# THW_Schematic_v1_0_0.net
KiCad netlist of a schematic drawn in EAGLE
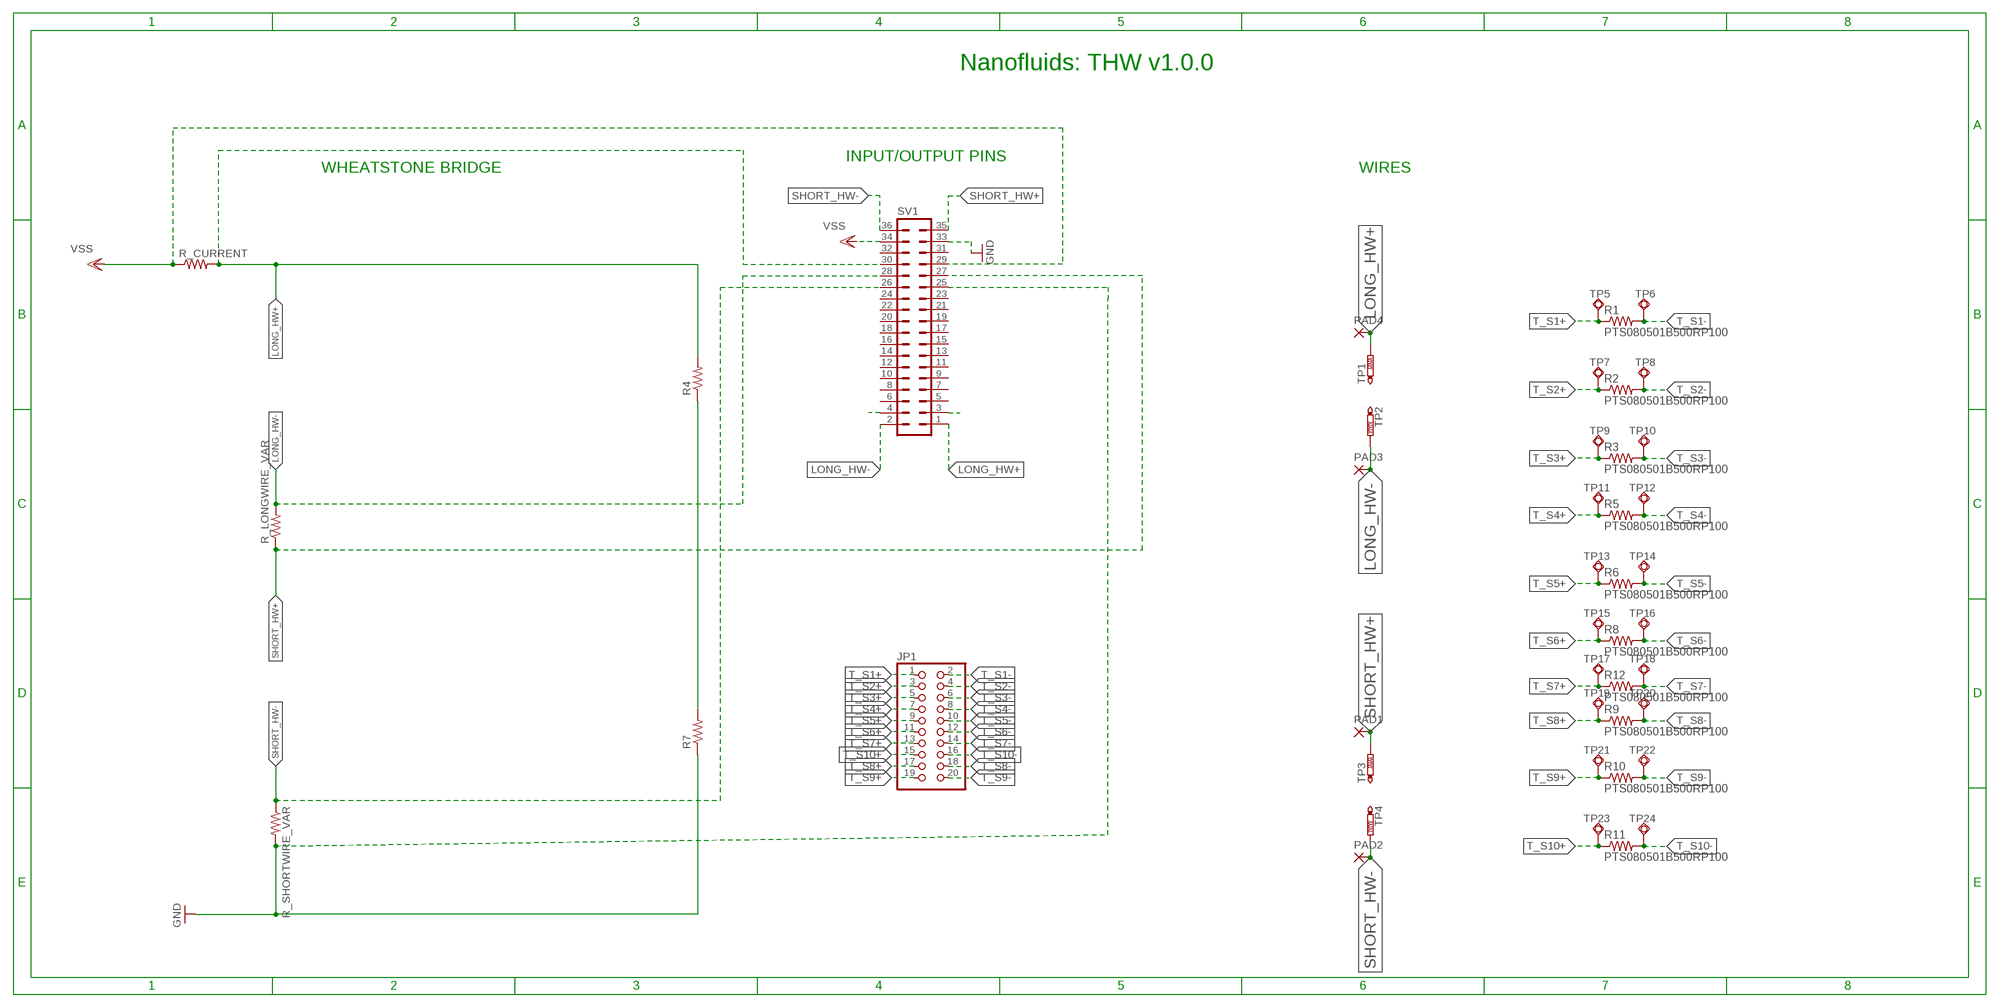
[diagram p0: schematic, sheet 1]

(export (version "E")
  (design (tool "Eeschema 10.0.6"))
  (components
    (comp (ref "JP1")
      (value "PINHD-2X10")
      (footprint "eagle-import:2X10")
      (libsource (lib "eagle-import") (part "PINHD-2X10"))
    )
    (comp (ref "PAD1")
      (value "SMD5")
      (footprint "eagle-import:SMD2,54-5,08")
      (libsource (lib "eagle-import") (part "SMD5"))
    )
    (comp (ref "PAD2")
      (value "SMD5")
      (footprint "eagle-import:SMD2,54-5,08")
      (libsource (lib "eagle-import") (part "SMD5"))
    )
    (comp (ref "PAD3")
      (value "SMD5")
      (footprint "eagle-import:SMD2,54-5,08")
      (libsource (lib "eagle-import") (part "SMD5"))
    )
    (comp (ref "PAD4")
      (value "SMD5")
      (footprint "eagle-import:SMD2,54-5,08")
      (libsource (lib "eagle-import") (part "SMD5"))
    )
    (comp (ref "R1")
      (value "PTS080501B500RP100")
      (footprint "eagle-import:RESC2012X60")
      (fields (field (name "MF") "Vishay"))
      (libsource (lib "eagle-import") (part "PTS080501B500RP100"))
    )
    (comp (ref "R2")
      (value "PTS080501B500RP100")
      (footprint "eagle-import:RESC2012X60")
      (fields (field (name "MF") "Vishay"))
      (libsource (lib "eagle-import") (part "PTS080501B500RP100"))
    )
    (comp (ref "R3")
      (value "PTS080501B500RP100")
      (footprint "eagle-import:RESC2012X60")
      (fields (field (name "MF") "Vishay"))
      (libsource (lib "eagle-import") (part "PTS080501B500RP100"))
    )
    (comp (ref "R4")
      (value "R-US_M0805")
      (footprint "eagle-import:M0805")
      (libsource (lib "eagle-import") (part "R-US_M0805"))
    )
    (comp (ref "R5")
      (value "PTS080501B500RP100")
      (footprint "eagle-import:RESC2012X60")
      (fields (field (name "MF") "Vishay"))
      (libsource (lib "eagle-import") (part "PTS080501B500RP100"))
    )
    (comp (ref "R6")
      (value "PTS080501B500RP100")
      (footprint "eagle-import:RESC2012X60")
      (fields (field (name "MF") "Vishay"))
      (libsource (lib "eagle-import") (part "PTS080501B500RP100"))
    )
    (comp (ref "R7")
      (value "R-US_M0805")
      (footprint "eagle-import:M0805")
      (libsource (lib "eagle-import") (part "R-US_M0805"))
    )
    (comp (ref "R8")
      (value "PTS080501B500RP100")
      (footprint "eagle-import:RESC2012X60")
      (fields (field (name "MF") "Vishay"))
      (libsource (lib "eagle-import") (part "PTS080501B500RP100"))
    )
    (comp (ref "R9")
      (value "PTS080501B500RP100")
      (footprint "eagle-import:RESC2012X60")
      (fields (field (name "MF") "Vishay"))
      (libsource (lib "eagle-import") (part "PTS080501B500RP100"))
    )
    (comp (ref "R10")
      (value "PTS080501B500RP100")
      (footprint "eagle-import:RESC2012X60")
      (fields (field (name "MF") "Vishay"))
      (libsource (lib "eagle-import") (part "PTS080501B500RP100"))
    )
    (comp (ref "R11")
      (value "PTS080501B500RP100")
      (footprint "eagle-import:RESC2012X60")
      (fields (field (name "MF") "Vishay"))
      (libsource (lib "eagle-import") (part "PTS080501B500RP100"))
    )
    (comp (ref "R12")
      (value "PTS080501B500RP100")
      (footprint "eagle-import:RESC2012X60")
      (fields (field (name "MF") "Vishay"))
      (libsource (lib "eagle-import") (part "PTS080501B500RP100"))
    )
    (comp (ref "R_CURRENT")
      (value "R-US_M0805")
      (footprint "eagle-import:M0805")
      (libsource (lib "eagle-import") (part "R-US_M0805"))
    )
    (comp (ref "R_LONGWIRE_VAR")
      (value "R-US_M0805")
      (footprint "eagle-import:M0805")
      (libsource (lib "eagle-import") (part "R-US_M0805"))
    )
    (comp (ref "R_SHORTWIRE_VAR")
      (value "R-US_M0805")
      (footprint "eagle-import:M0805")
      (libsource (lib "eagle-import") (part "R-US_M0805"))
    )
    (comp (ref "SV1")
      (value "MA18-2")
      (footprint "eagle-import:MA18-2")
      (libsource (lib "eagle-import") (part "MA18-2"))
    )
    (comp (ref "TP1")
      (value "PTR1TP20R")
      (footprint "eagle-import:TP20R")
      (libsource (lib "eagle-import") (part "PTR1TP20R"))
    )
    (comp (ref "TP2")
      (value "PTR1TP20R")
      (footprint "eagle-import:TP20R")
      (libsource (lib "eagle-import") (part "PTR1TP20R"))
    )
    (comp (ref "TP3")
      (value "PTR1TP20R")
      (footprint "eagle-import:TP20R")
      (libsource (lib "eagle-import") (part "PTR1TP20R"))
    )
    (comp (ref "TP4")
      (value "PTR1TP20R")
      (footprint "eagle-import:TP20R")
      (libsource (lib "eagle-import") (part "PTR1TP20R"))
    )
    (comp (ref "TP5")
      (value "TPSQTP09SQ")
      (footprint "eagle-import:TP09SQ")
      (libsource (lib "eagle-import") (part "TPSQTP09SQ"))
    )
    (comp (ref "TP6")
      (value "TPSQTP09SQ")
      (footprint "eagle-import:TP09SQ")
      (libsource (lib "eagle-import") (part "TPSQTP09SQ"))
    )
    (comp (ref "TP7")
      (value "TPSQTP09SQ")
      (footprint "eagle-import:TP09SQ")
      (libsource (lib "eagle-import") (part "TPSQTP09SQ"))
    )
    (comp (ref "TP8")
      (value "TPSQTP09SQ")
      (footprint "eagle-import:TP09SQ")
      (libsource (lib "eagle-import") (part "TPSQTP09SQ"))
    )
    (comp (ref "TP9")
      (value "TPSQTP09SQ")
      (footprint "eagle-import:TP09SQ")
      (libsource (lib "eagle-import") (part "TPSQTP09SQ"))
    )
    (comp (ref "TP10")
      (value "TPSQTP09SQ")
      (footprint "eagle-import:TP09SQ")
      (libsource (lib "eagle-import") (part "TPSQTP09SQ"))
    )
    (comp (ref "TP11")
      (value "TPSQTP09SQ")
      (footprint "eagle-import:TP09SQ")
      (libsource (lib "eagle-import") (part "TPSQTP09SQ"))
    )
    (comp (ref "TP12")
      (value "TPSQTP09SQ")
      (footprint "eagle-import:TP09SQ")
      (libsource (lib "eagle-import") (part "TPSQTP09SQ"))
    )
    (comp (ref "TP13")
      (value "TPSQTP09SQ")
      (footprint "eagle-import:TP09SQ")
      (libsource (lib "eagle-import") (part "TPSQTP09SQ"))
    )
    (comp (ref "TP14")
      (value "TPSQTP09SQ")
      (footprint "eagle-import:TP09SQ")
      (libsource (lib "eagle-import") (part "TPSQTP09SQ"))
    )
    (comp (ref "TP15")
      (value "TPSQTP09SQ")
      (footprint "eagle-import:TP09SQ")
      (libsource (lib "eagle-import") (part "TPSQTP09SQ"))
    )
    (comp (ref "TP16")
      (value "TPSQTP09SQ")
      (footprint "eagle-import:TP09SQ")
      (libsource (lib "eagle-import") (part "TPSQTP09SQ"))
    )
    (comp (ref "TP17")
      (value "TPSQTP09SQ")
      (footprint "eagle-import:TP09SQ")
      (libsource (lib "eagle-import") (part "TPSQTP09SQ"))
    )
    (comp (ref "TP18")
      (value "TPSQTP09SQ")
      (footprint "eagle-import:TP09SQ")
      (libsource (lib "eagle-import") (part "TPSQTP09SQ"))
    )
    (comp (ref "TP19")
      (value "TPSQTP09SQ")
      (footprint "eagle-import:TP09SQ")
      (libsource (lib "eagle-import") (part "TPSQTP09SQ"))
    )
    (comp (ref "TP20")
      (value "TPSQTP09SQ")
      (footprint "eagle-import:TP09SQ")
      (libsource (lib "eagle-import") (part "TPSQTP09SQ"))
    )
    (comp (ref "TP21")
      (value "TPSQTP09SQ")
      (footprint "eagle-import:TP09SQ")
      (libsource (lib "eagle-import") (part "TPSQTP09SQ"))
    )
    (comp (ref "TP22")
      (value "TPSQTP09SQ")
      (footprint "eagle-import:TP09SQ")
      (libsource (lib "eagle-import") (part "TPSQTP09SQ"))
    )
    (comp (ref "TP23")
      (value "TPSQTP09SQ")
      (footprint "eagle-import:TP09SQ")
      (libsource (lib "eagle-import") (part "TPSQTP09SQ"))
    )
    (comp (ref "TP24")
      (value "TPSQTP09SQ")
      (footprint "eagle-import:TP09SQ")
      (libsource (lib "eagle-import") (part "TPSQTP09SQ"))
    )
  )
  (nets
    (net (code "1") (name "GND") (class "Default")
      (node (ref "R7") (pin "1") (pinfunction "1_1") (pintype "passive"))
      (node (ref "R_SHORTWIRE_VAR") (pin "2") (pinfunction "2_2") (pintype "passive"))
      (node (ref "SV1") (pin "25") (pinfunction "25_25") (pintype "passive"))
      (node (ref "SV1") (pin "33") (pinfunction "33_33") (pintype "passive"))
    )
    (net (code "2") (name "LONG_HW+") (class "Default")
      (node (ref "PAD4") (pin "1") (pinfunction "P_1") (pintype "passive"))
      (node (ref "R4") (pin "2") (pinfunction "2_2") (pintype "passive"))
      (node (ref "R_CURRENT") (pin "2") (pinfunction "2_2") (pintype "passive"))
      (node (ref "SV1") (pin "1") (pinfunction "1_1") (pintype "passive"))
      (node (ref "SV1") (pin "30") (pinfunction "30_30") (pintype "passive"))
      (node (ref "TP1") (pin "TP") (pinfunction "TP_TP") (pintype "input"))
    )
    (net (code "3") (name "LONG_HW-") (class "Default")
      (node (ref "PAD3") (pin "1") (pinfunction "P_1") (pintype "passive"))
      (node (ref "R_LONGWIRE_VAR") (pin "2") (pinfunction "2_2") (pintype "passive"))
      (node (ref "SV1") (pin "2") (pinfunction "2_2") (pintype "passive"))
      (node (ref "SV1") (pin "28") (pinfunction "28_28") (pintype "passive"))
      (node (ref "TP2") (pin "TP") (pinfunction "TP_TP") (pintype "input"))
    )
    (net (code "4") (name "Net-(R4-Pad1)") (class "Default")
      (node (ref "R4") (pin "1") (pinfunction "1_1") (pintype "passive"))
      (node (ref "R7") (pin "2") (pinfunction "2_2") (pintype "passive"))
    )
    (net (code "5") (name "SHORT_HW+") (class "Default")
      (node (ref "PAD1") (pin "1") (pinfunction "P_1") (pintype "passive"))
      (node (ref "R_LONGWIRE_VAR") (pin "1") (pinfunction "1_1") (pintype "passive"))
      (node (ref "SV1") (pin "27") (pinfunction "27_27") (pintype "passive"))
      (node (ref "SV1") (pin "35") (pinfunction "35_35") (pintype "passive"))
      (node (ref "TP3") (pin "TP") (pinfunction "TP_TP") (pintype "input"))
    )
    (net (code "6") (name "SHORT_HW-") (class "Default")
      (node (ref "PAD2") (pin "1") (pinfunction "P_1") (pintype "passive"))
      (node (ref "R_SHORTWIRE_VAR") (pin "1") (pinfunction "1_1") (pintype "passive"))
      (node (ref "SV1") (pin "26") (pinfunction "26_26") (pintype "passive"))
      (node (ref "SV1") (pin "36") (pinfunction "36_36") (pintype "passive"))
      (node (ref "TP4") (pin "TP") (pinfunction "TP_TP") (pintype "input"))
    )
    (net (code "7") (name "T_S1+") (class "Default")
      (node (ref "JP1") (pin "1") (pinfunction "1_1") (pintype "passive"))
      (node (ref "R1") (pin "1") (pinfunction "1_1") (pintype "passive"))
      (node (ref "TP5") (pin "TP") (pinfunction "TP_TP") (pintype "input"))
    )
    (net (code "8") (name "T_S1-") (class "Default")
      (node (ref "JP1") (pin "2") (pinfunction "2_2") (pintype "passive"))
      (node (ref "R1") (pin "2") (pinfunction "2_2") (pintype "passive"))
      (node (ref "TP6") (pin "TP") (pinfunction "TP_TP") (pintype "input"))
    )
    (net (code "9") (name "T_S2+") (class "Default")
      (node (ref "JP1") (pin "3") (pinfunction "3_3") (pintype "passive"))
      (node (ref "R2") (pin "1") (pinfunction "1_1") (pintype "passive"))
      (node (ref "TP7") (pin "TP") (pinfunction "TP_TP") (pintype "input"))
    )
    (net (code "10") (name "T_S2-") (class "Default")
      (node (ref "JP1") (pin "4") (pinfunction "4_4") (pintype "passive"))
      (node (ref "R2") (pin "2") (pinfunction "2_2") (pintype "passive"))
      (node (ref "TP8") (pin "TP") (pinfunction "TP_TP") (pintype "input"))
    )
    (net (code "11") (name "T_S3+") (class "Default")
      (node (ref "JP1") (pin "5") (pinfunction "5_5") (pintype "passive"))
      (node (ref "R3") (pin "1") (pinfunction "1_1") (pintype "passive"))
      (node (ref "TP9") (pin "TP") (pinfunction "TP_TP") (pintype "input"))
    )
    (net (code "12") (name "T_S3-") (class "Default")
      (node (ref "JP1") (pin "6") (pinfunction "6_6") (pintype "passive"))
      (node (ref "R3") (pin "2") (pinfunction "2_2") (pintype "passive"))
      (node (ref "TP10") (pin "TP") (pinfunction "TP_TP") (pintype "input"))
    )
    (net (code "13") (name "T_S4+") (class "Default")
      (node (ref "JP1") (pin "7") (pinfunction "7_7") (pintype "passive"))
      (node (ref "R5") (pin "1") (pinfunction "1_1") (pintype "passive"))
      (node (ref "TP11") (pin "TP") (pinfunction "TP_TP") (pintype "input"))
    )
    (net (code "14") (name "T_S4-") (class "Default")
      (node (ref "JP1") (pin "8") (pinfunction "8_8") (pintype "passive"))
      (node (ref "R5") (pin "2") (pinfunction "2_2") (pintype "passive"))
      (node (ref "TP12") (pin "TP") (pinfunction "TP_TP") (pintype "input"))
    )
    (net (code "15") (name "T_S5+") (class "Default")
      (node (ref "JP1") (pin "9") (pinfunction "9_9") (pintype "passive"))
      (node (ref "R6") (pin "1") (pinfunction "1_1") (pintype "passive"))
      (node (ref "TP13") (pin "TP") (pinfunction "TP_TP") (pintype "input"))
    )
    (net (code "16") (name "T_S5-") (class "Default")
      (node (ref "JP1") (pin "10") (pinfunction "10_10") (pintype "passive"))
      (node (ref "R6") (pin "2") (pinfunction "2_2") (pintype "passive"))
      (node (ref "TP14") (pin "TP") (pinfunction "TP_TP") (pintype "input"))
    )
    (net (code "17") (name "T_S6+") (class "Default")
      (node (ref "JP1") (pin "11") (pinfunction "11_11") (pintype "passive"))
      (node (ref "R8") (pin "1") (pinfunction "1_1") (pintype "passive"))
      (node (ref "TP15") (pin "TP") (pinfunction "TP_TP") (pintype "input"))
    )
    (net (code "18") (name "T_S6-") (class "Default")
      (node (ref "JP1") (pin "12") (pinfunction "12_12") (pintype "passive"))
      (node (ref "R8") (pin "2") (pinfunction "2_2") (pintype "passive"))
      (node (ref "TP16") (pin "TP") (pinfunction "TP_TP") (pintype "input"))
    )
    (net (code "19") (name "T_S7+") (class "Default")
      (node (ref "R12") (pin "1") (pinfunction "1_1") (pintype "passive"))
      (node (ref "TP17") (pin "TP") (pinfunction "TP_TP") (pintype "input"))
    )
    (net (code "20") (name "T_S7-") (class "Default")
      (node (ref "JP1") (pin "14") (pinfunction "14_14") (pintype "passive"))
      (node (ref "R12") (pin "2") (pinfunction "2_2") (pintype "passive"))
      (node (ref "TP18") (pin "TP") (pinfunction "TP_TP") (pintype "input"))
    )
    (net (code "21") (name "T_S8+") (class "Default")
      (node (ref "JP1") (pin "17") (pinfunction "17_17") (pintype "passive"))
      (node (ref "R9") (pin "1") (pinfunction "1_1") (pintype "passive"))
      (node (ref "TP19") (pin "TP") (pinfunction "TP_TP") (pintype "input"))
    )
    (net (code "22") (name "T_S8-") (class "Default")
      (node (ref "JP1") (pin "18") (pinfunction "18_18") (pintype "passive"))
      (node (ref "R9") (pin "2") (pinfunction "2_2") (pintype "passive"))
      (node (ref "TP20") (pin "TP") (pinfunction "TP_TP") (pintype "input"))
    )
    (net (code "23") (name "T_S9+") (class "Default")
      (node (ref "JP1") (pin "19") (pinfunction "19_19") (pintype "passive"))
      (node (ref "R10") (pin "1") (pinfunction "1_1") (pintype "passive"))
      (node (ref "TP21") (pin "TP") (pinfunction "TP_TP") (pintype "input"))
    )
    (net (code "24") (name "T_S9-") (class "Default")
      (node (ref "JP1") (pin "20") (pinfunction "20_20") (pintype "passive"))
      (node (ref "R10") (pin "2") (pinfunction "2_2") (pintype "passive"))
      (node (ref "TP22") (pin "TP") (pinfunction "TP_TP") (pintype "input"))
    )
    (net (code "25") (name "T_S10+") (class "Default")
      (node (ref "JP1") (pin "15") (pinfunction "15_15") (pintype "passive"))
      (node (ref "R11") (pin "1") (pinfunction "1_1") (pintype "passive"))
      (node (ref "TP23") (pin "TP") (pinfunction "TP_TP") (pintype "input"))
    )
    (net (code "26") (name "T_S10-") (class "Default")
      (node (ref "JP1") (pin "16") (pinfunction "16_16") (pintype "passive"))
      (node (ref "R11") (pin "2") (pinfunction "2_2") (pintype "passive"))
      (node (ref "TP24") (pin "TP") (pinfunction "TP_TP") (pintype "input"))
    )
    (net (code "27") (name "VSS") (class "Default")
      (node (ref "R_CURRENT") (pin "1") (pinfunction "1_1") (pintype "passive"))
      (node (ref "SV1") (pin "29") (pinfunction "29_29") (pintype "passive"))
      (node (ref "SV1") (pin "34") (pinfunction "34_34") (pintype "passive"))
    )
    (net (code "28") (name "unconnected-(JP1-Pad13)") (class "Default")
      (node (ref "JP1") (pin "13") (pinfunction "13_13") (pintype "passive"))
    )
    (net (code "29") (name "unconnected-(SV1-Pad3)") (class "Default")
      (node (ref "SV1") (pin "3") (pinfunction "3_3") (pintype "passive"))
    )
    (net (code "30") (name "unconnected-(SV1-Pad4)") (class "Default")
      (node (ref "SV1") (pin "4") (pinfunction "4_4") (pintype "passive"))
    )
    (net (code "31") (name "unconnected-(SV1-Pad5)") (class "Default")
      (node (ref "SV1") (pin "5") (pinfunction "5_5") (pintype "passive"))
    )
    (net (code "32") (name "unconnected-(SV1-Pad6)") (class "Default")
      (node (ref "SV1") (pin "6") (pinfunction "6_6") (pintype "passive"))
    )
    (net (code "33") (name "unconnected-(SV1-Pad7)") (class "Default")
      (node (ref "SV1") (pin "7") (pinfunction "7_7") (pintype "passive"))
    )
    (net (code "34") (name "unconnected-(SV1-Pad8)") (class "Default")
      (node (ref "SV1") (pin "8") (pinfunction "8_8") (pintype "passive"))
    )
    (net (code "35") (name "unconnected-(SV1-Pad9)") (class "Default")
      (node (ref "SV1") (pin "9") (pinfunction "9_9") (pintype "passive"))
    )
    (net (code "36") (name "unconnected-(SV1-Pad10)") (class "Default")
      (node (ref "SV1") (pin "10") (pinfunction "10_10") (pintype "passive"))
    )
    (net (code "37") (name "unconnected-(SV1-Pad11)") (class "Default")
      (node (ref "SV1") (pin "11") (pinfunction "11_11") (pintype "passive"))
    )
    (net (code "38") (name "unconnected-(SV1-Pad12)") (class "Default")
      (node (ref "SV1") (pin "12") (pinfunction "12_12") (pintype "passive"))
    )
    (net (code "39") (name "unconnected-(SV1-Pad13)") (class "Default")
      (node (ref "SV1") (pin "13") (pinfunction "13_13") (pintype "passive"))
    )
    (net (code "40") (name "unconnected-(SV1-Pad14)") (class "Default")
      (node (ref "SV1") (pin "14") (pinfunction "14_14") (pintype "passive"))
    )
    (net (code "41") (name "unconnected-(SV1-Pad15)") (class "Default")
      (node (ref "SV1") (pin "15") (pinfunction "15_15") (pintype "passive"))
    )
    (net (code "42") (name "unconnected-(SV1-Pad16)") (class "Default")
      (node (ref "SV1") (pin "16") (pinfunction "16_16") (pintype "passive"))
    )
    (net (code "43") (name "unconnected-(SV1-Pad17)") (class "Default")
      (node (ref "SV1") (pin "17") (pinfunction "17_17") (pintype "passive"))
    )
    (net (code "44") (name "unconnected-(SV1-Pad18)") (class "Default")
      (node (ref "SV1") (pin "18") (pinfunction "18_18") (pintype "passive"))
    )
    (net (code "45") (name "unconnected-(SV1-Pad19)") (class "Default")
      (node (ref "SV1") (pin "19") (pinfunction "19_19") (pintype "passive"))
    )
    (net (code "46") (name "unconnected-(SV1-Pad20)") (class "Default")
      (node (ref "SV1") (pin "20") (pinfunction "20_20") (pintype "passive"))
    )
    (net (code "47") (name "unconnected-(SV1-Pad21)") (class "Default")
      (node (ref "SV1") (pin "21") (pinfunction "21_21") (pintype "passive"))
    )
    (net (code "48") (name "unconnected-(SV1-Pad22)") (class "Default")
      (node (ref "SV1") (pin "22") (pinfunction "22_22") (pintype "passive"))
    )
    (net (code "49") (name "unconnected-(SV1-Pad23)") (class "Default")
      (node (ref "SV1") (pin "23") (pinfunction "23_23") (pintype "passive"))
    )
    (net (code "50") (name "unconnected-(SV1-Pad24)") (class "Default")
      (node (ref "SV1") (pin "24") (pinfunction "24_24") (pintype "passive"))
    )
    (net (code "51") (name "unconnected-(SV1-Pad31)") (class "Default")
      (node (ref "SV1") (pin "31") (pinfunction "31_31") (pintype "passive"))
    )
    (net (code "52") (name "unconnected-(SV1-Pad32)") (class "Default")
      (node (ref "SV1") (pin "32") (pinfunction "32_32") (pintype "passive"))
    )
  )
)
